# ArbPwrBoost_P5.net
KiCad netlist of a schematic drawn in Altium Designer
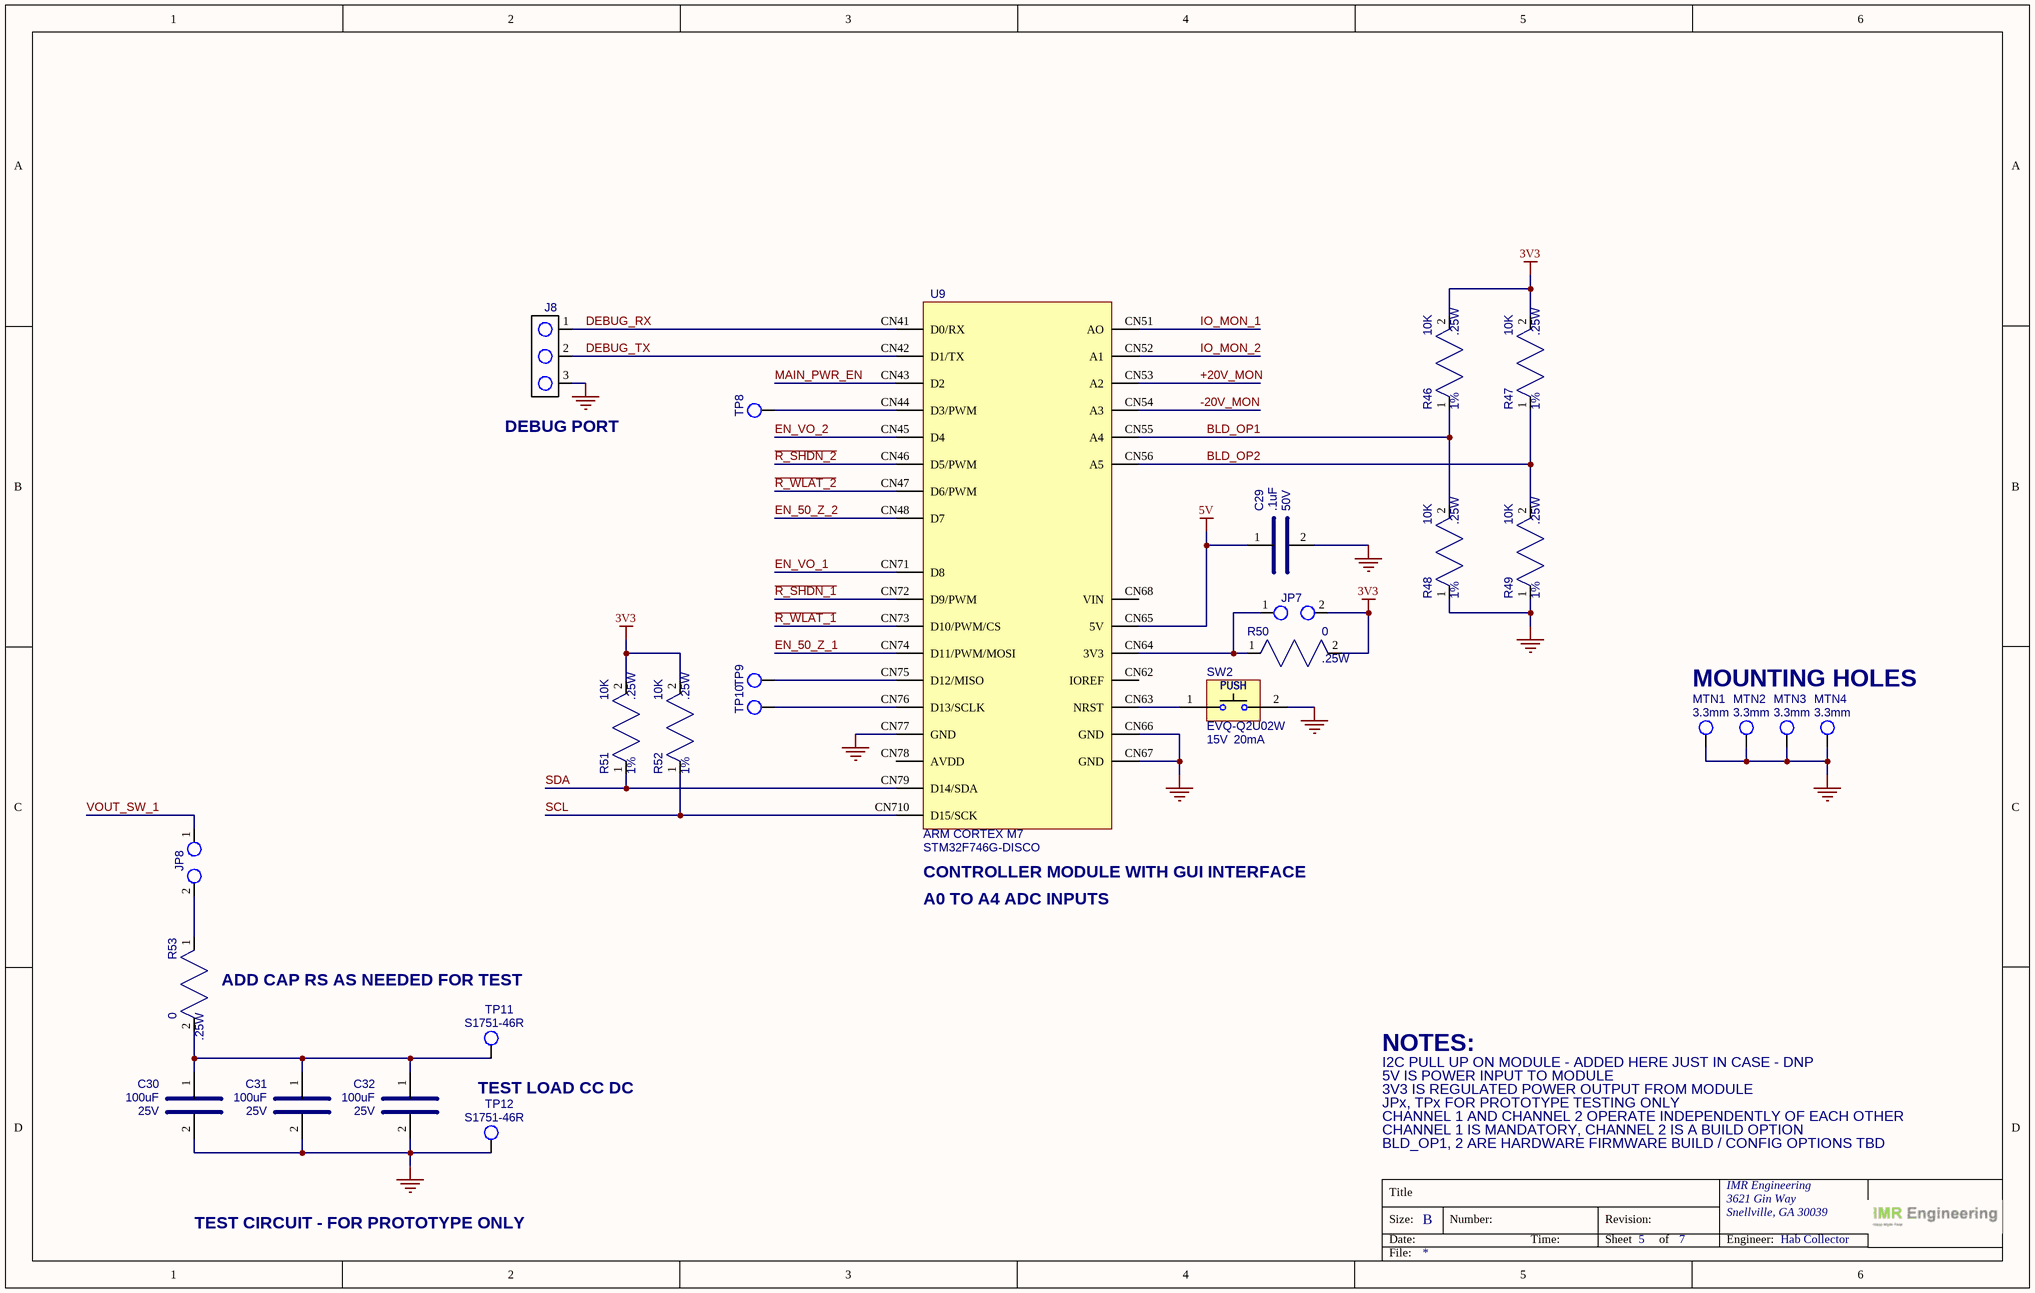
[diagram p0: ArbPwrBoost_P5.SchDoc]

(export (version "E")
  (design (tool "Eeschema 10.0.6"))
  (components
    (comp (ref "C29")
      (value ".1uF")
      (footprint "CAP_0805")
      (description "CAP CER 0.1UF 50V X7R 0805")
      (fields
        (field (name "MFG") "KYOCERA AVX")
        (field (name "VOLTAGE") "50V")
        (field (name "Comment") "KGM21NR71H104KT")
      )
      (libsource (lib "IMR_LIB_SCH_R2") (part "CAP_SMD_0.1UF_50V_0805"))
    )
    (comp (ref "C30")
      (value "100uF")
      (footprint "CAPC6153X670N")
      (description "CAP CER 100UF 25V X7S SMD")
      (fields
        (field (name "MFG") "Murata Electronics")
        (field (name "VOLTAGE") "25V")
        (field (name "Comment") "KCM55WC71E107MH13L")
      )
      (libsource (lib "IMR_LIB_SCH_R2") (part "CAP_SMD_100UF_25V_SMD"))
    )
    (comp (ref "C31")
      (value "100uF")
      (footprint "CAPC6153X670N")
      (description "CAP CER 100UF 25V X7S SMD")
      (fields
        (field (name "MFG") "Murata Electronics")
        (field (name "VOLTAGE") "25V")
        (field (name "Comment") "KCM55WC71E107MH13L")
      )
      (libsource (lib "IMR_LIB_SCH_R2") (part "CAP_SMD_100UF_25V_SMD"))
    )
    (comp (ref "C32")
      (value "100uF")
      (footprint "CAPC6153X670N")
      (description "CAP CER 100UF 25V X7S SMD")
      (fields
        (field (name "MFG") "Murata Electronics")
        (field (name "VOLTAGE") "25V")
        (field (name "Comment") "KCM55WC71E107MH13L")
      )
      (libsource (lib "IMR_LIB_SCH_R2") (part "CAP_SMD_100UF_25V_SMD"))
    )
    (comp (ref "J8")
      (value "PREC003SFAN-RC")
      (footprint "HDR_1X3_100MILL")
      (description "CONN HEADER VERT 3POS 2.54MM")
      (fields (field (name "MFG") "Sullins Connector Solutions"))
      (libsource (lib "IMR_LIB_SCH_R2") (part "CONN_HEADER_3P_100MIL_VERT"))
    )
    (comp (ref "JP7")
      (value "PREC002SFAN-RC")
      (footprint "HDR_1X2_100MILL")
      (description "CONN HEADER VERT 2POS 2.54MM")
      (fields (field (name "MFG") "Sullins Connector Solutions"))
      (libsource (lib "IMR_LIB_SCH_R2") (part "CONN_JUMPER_2P_100MIL_VERT"))
    )
    (comp (ref "JP8")
      (value "PREC002SFAN-RC")
      (footprint "HDR_1X2_100MILL")
      (description "CONN HEADER VERT 2POS 2.54MM")
      (fields (field (name "MFG") "Sullins Connector Solutions"))
      (libsource (lib "IMR_LIB_SCH_R2") (part "CONN_JUMPER_2P_100MIL_VERT"))
    )
    (comp (ref "MTN1")
      (value "~")
      (footprint "PMG_MT_HOLE_3.3MM")
      (description "MOUNTING HOLE 3.3MM")
      (fields (field (name "HOLE SIZE") "3.3mm"))
      (libsource (lib "IMR_LIB_SCH_R2") (part "MTN_HOLE_3.3MM"))
    )
    (comp (ref "MTN2")
      (value "~")
      (footprint "PMG_MT_HOLE_3.3MM")
      (description "MOUNTING HOLE 3.3MM")
      (fields (field (name "HOLE SIZE") "3.3mm"))
      (libsource (lib "IMR_LIB_SCH_R2") (part "MTN_HOLE_3.3MM"))
    )
    (comp (ref "MTN3")
      (value "~")
      (footprint "PMG_MT_HOLE_3.3MM")
      (description "MOUNTING HOLE 3.3MM")
      (fields (field (name "HOLE SIZE") "3.3mm"))
      (libsource (lib "IMR_LIB_SCH_R2") (part "MTN_HOLE_3.3MM"))
    )
    (comp (ref "MTN4")
      (value "~")
      (footprint "PMG_MT_HOLE_3.3MM")
      (description "MOUNTING HOLE 3.3MM")
      (fields (field (name "HOLE SIZE") "3.3mm"))
      (libsource (lib "IMR_LIB_SCH_R2") (part "MTN_HOLE_3.3MM"))
    )
    (comp (ref "R46")
      (value "10K")
      (footprint "RES_0805")
      (description "RES SMD 10K OHM 1% 1/4W 0805")
      (fields
        (field (name "MFG") "Yageo")
        (field (name "POWER") ".25W")
        (field (name "TOLERANCE") "1%")
        (field (name "Comment") "RC0805FR-7W10KL")
      )
      (libsource (lib "IMR_LIB_SCH_R2") (part "RES_SMD_10K_0805_1/4W_1%"))
    )
    (comp (ref "R47")
      (value "10K")
      (footprint "RES_0805")
      (description "RES SMD 10K OHM 1% 1/4W 0805")
      (fields
        (field (name "MFG") "Yageo")
        (field (name "POWER") ".25W")
        (field (name "TOLERANCE") "1%")
        (field (name "Comment") "RC0805FR-7W10KL")
      )
      (libsource (lib "IMR_LIB_SCH_R2") (part "RES_SMD_10K_0805_1/4W_1%"))
    )
    (comp (ref "R48")
      (value "10K")
      (footprint "RES_0805")
      (description "RES SMD 10K OHM 1% 1/4W 0805")
      (fields
        (field (name "MFG") "Yageo")
        (field (name "POWER") ".25W")
        (field (name "TOLERANCE") "1%")
        (field (name "Comment") "RC0805FR-7W10KL")
      )
      (libsource (lib "IMR_LIB_SCH_R2") (part "RES_SMD_10K_0805_1/4W_1%"))
    )
    (comp (ref "R49")
      (value "10K")
      (footprint "RES_0805")
      (description "RES SMD 10K OHM 1% 1/4W 0805")
      (fields
        (field (name "MFG") "Yageo")
        (field (name "POWER") ".25W")
        (field (name "TOLERANCE") "1%")
        (field (name "Comment") "RC0805FR-7W10KL")
      )
      (libsource (lib "IMR_LIB_SCH_R2") (part "RES_SMD_10K_0805_1/4W_1%"))
    )
    (comp (ref "R50")
      (value "0")
      (footprint "RES_0805")
      (description "RES SMD 0 OHM 1% 1/8W 0805")
      (fields (field (name "MFG") "Yageo") (field (name "TOLERANCE") "1%") (field (name "POWER") ".25W"))
      (libsource (lib "IMR_LIB_SCH_R2") (part "RES_SMD_0_0805_1/8W_1%"))
    )
    (comp (ref "R51")
      (value "10K")
      (footprint "RES_0805")
      (description "RES SMD 10K OHM 1% 1/4W 0805")
      (fields
        (field (name "MFG") "Yageo")
        (field (name "POWER") ".25W")
        (field (name "TOLERANCE") "1%")
        (field (name "Comment") "RC0805FR-7W10KL")
      )
      (libsource (lib "IMR_LIB_SCH_R2") (part "RES_SMD_10K_0805_1/4W_1%"))
    )
    (comp (ref "R52")
      (value "10K")
      (footprint "RES_0805")
      (description "RES SMD 10K OHM 1% 1/4W 0805")
      (fields
        (field (name "MFG") "Yageo")
        (field (name "POWER") ".25W")
        (field (name "TOLERANCE") "1%")
        (field (name "Comment") "RC0805FR-7W10KL")
      )
      (libsource (lib "IMR_LIB_SCH_R2") (part "RES_SMD_10K_0805_1/4W_1%"))
    )
    (comp (ref "R53")
      (value "0")
      (footprint "RES_0805")
      (description "RES SMD 0 OHM 1% 1/8W 0805")
      (fields (field (name "MFG") "Yageo") (field (name "TOLERANCE") "1%") (field (name "POWER") ".25W"))
      (libsource (lib "IMR_LIB_SCH_R2") (part "RES_SMD_0_0805_1/8W_1%"))
    )
    (comp (ref "SW2")
      (value "15V")
      (footprint "PANASONIC_EVQ-Q2U02W")
      (description "SWITCH TACTILE SPST-NO 0.02A 15V")
      (fields
        (field (name "MFG") "American Zettler")
        (field (name "MFG_PN") "EVQ-Q2U02W")
        (field (name "CURRENT") "20mA")
        (field (name "Comment") "EVQ-Q2U02W")
      )
      (libsource (lib "IMR_LIB_SCH_R2") (part "SWITCH_EVQ-Q2U02W"))
    )
    (comp (ref "TP8")
      (value "~")
      (footprint "TEST_POINT_20MIL_TH")
      (description "TEST POINT TH 20MIL HOLE")
      (libsource (lib "IMR_LIB_SCH_R2") (part "CONN_TEST_POINT_TH_PAD_20MIL"))
    )
    (comp (ref "TP9")
      (value "~")
      (footprint "TEST_POINT_20MIL_TH")
      (description "TEST POINT TH 20MIL HOLE")
      (libsource (lib "IMR_LIB_SCH_R2") (part "CONN_TEST_POINT_TH_PAD_20MIL"))
    )
    (comp (ref "TP10")
      (value "~")
      (footprint "TEST_POINT_20MIL_TH")
      (description "TEST POINT TH 20MIL HOLE")
      (libsource (lib "IMR_LIB_SCH_R2") (part "CONN_TEST_POINT_TH_PAD_20MIL"))
    )
    (comp (ref "TP11")
      (value "S1751-46R")
      (footprint "HARWIN_S1751")
      (description "PCB TEST POINT CONNECT")
      (fields (field (name "MFG") "Harwin Inc") (field (name "MFG_PN") "S1751-46R"))
      (libsource (lib "IMR_LIB_SCH_R2") (part "CONN_TEST_POINT_S1751-46R"))
    )
    (comp (ref "TP12")
      (value "S1751-46R")
      (footprint "HARWIN_S1751")
      (description "PCB TEST POINT CONNECT")
      (fields (field (name "MFG") "Harwin Inc") (field (name "MFG_PN") "S1751-46R"))
      (libsource (lib "IMR_LIB_SCH_R2") (part "CONN_TEST_POINT_S1751-46R"))
    )
    (comp (ref "U9")
      (value "ARM CORTEX M7")
      (footprint "STM32F746G-DISCO")
      (description "DISCOVERY STM32 F7 EVAL BRD")
      (fields
        (field (name "MFG") "ST Microlectronics")
        (field (name "MFG_PN") "STM32F746G-DISCO")
        (field (name "Comment") "STM32F746G-DISCO")
      )
      (libsource (lib "IMR_LIB_SCH_R2") (part "MODULE_STM32F746G-DISCO"))
    )
  )
  (nets
    (net (code "1") (name "/+20V_MON") (class "Default")
      (node (ref "U9") (pin "CN53") (pinfunction "A2_CN53") (pintype "passive"))
    )
    (net (code "2") (name "/-20V_MON") (class "Default")
      (node (ref "U9") (pin "CN54") (pinfunction "A3_CN54") (pintype "passive"))
    )
    (net (code "3") (name "/BLD_OP1") (class "Default")
      (node (ref "R46") (pin "1") (pinfunction "1_1") (pintype "passive"))
      (node (ref "R48") (pin "2") (pinfunction "2_2") (pintype "passive"))
      (node (ref "U9") (pin "CN55") (pinfunction "A4_CN55") (pintype "passive"))
    )
    (net (code "4") (name "/BLD_OP2") (class "Default")
      (node (ref "R47") (pin "1") (pinfunction "1_1") (pintype "passive"))
      (node (ref "R49") (pin "2") (pinfunction "2_2") (pintype "passive"))
      (node (ref "U9") (pin "CN56") (pinfunction "A5_CN56") (pintype "passive"))
    )
    (net (code "5") (name "/DEBUG_RX") (class "Default")
      (node (ref "J8") (pin "1") (pintype "passive"))
      (node (ref "U9") (pin "CN41") (pinfunction "D0/RX_CN41") (pintype "passive"))
    )
    (net (code "6") (name "/DEBUG_TX") (class "Default")
      (node (ref "J8") (pin "2") (pintype "passive"))
      (node (ref "U9") (pin "CN42") (pinfunction "D1/TX_CN42") (pintype "passive"))
    )
    (net (code "7") (name "/EN_50_Z_1") (class "Default")
      (node (ref "U9") (pin "CN74") (pinfunction "D11/PWM/MOSI_CN74") (pintype "passive"))
    )
    (net (code "8") (name "/EN_50_Z_2") (class "Default")
      (node (ref "U9") (pin "CN48") (pinfunction "D7_CN48") (pintype "passive"))
    )
    (net (code "9") (name "/EN_VO_1") (class "Default")
      (node (ref "U9") (pin "CN71") (pinfunction "D8_CN71") (pintype "passive"))
    )
    (net (code "10") (name "/EN_VO_2") (class "Default")
      (node (ref "U9") (pin "CN45") (pinfunction "D4_CN45") (pintype "passive"))
    )
    (net (code "11") (name "/IO_MON_1") (class "Default")
      (node (ref "U9") (pin "CN51") (pinfunction "AO_CN51") (pintype "passive"))
    )
    (net (code "12") (name "/IO_MON_2") (class "Default")
      (node (ref "U9") (pin "CN52") (pinfunction "A1_CN52") (pintype "passive"))
    )
    (net (code "13") (name "/MAIN_PWR_EN") (class "Default")
      (node (ref "U9") (pin "CN43") (pinfunction "D2_CN43") (pintype "passive"))
    )
    (net (code "14") (name "/SCL") (class "Default")
      (node (ref "R52") (pin "1") (pinfunction "1_1") (pintype "passive"))
      (node (ref "U9") (pin "CN710") (pinfunction "D15/SCK_CN710") (pintype "passive"))
    )
    (net (code "15") (name "/SDA") (class "Default")
      (node (ref "R51") (pin "1") (pinfunction "1_1") (pintype "passive"))
      (node (ref "U9") (pin "CN79") (pinfunction "D14/SDA_CN79") (pintype "passive"))
    )
    (net (code "16") (name "/VOUT_SW_1") (class "Default") (node (ref "JP8") (pin "1") (pintype "passive")))
    (net (code "17") (name "/~{R_SHDN_1}") (class "Default")
      (node (ref "U9") (pin "CN72") (pinfunction "D9/PWM_CN72") (pintype "passive"))
    )
    (net (code "18") (name "/~{R_SHDN_2}") (class "Default")
      (node (ref "U9") (pin "CN46") (pinfunction "D5/PWM_CN46") (pintype "passive"))
    )
    (net (code "19") (name "/~{R_WLAT_1}") (class "Default")
      (node (ref "U9") (pin "CN73") (pinfunction "D10/PWM/CS_CN73") (pintype "passive"))
    )
    (net (code "20") (name "/~{R_WLAT_2}") (class "Default")
      (node (ref "U9") (pin "CN47") (pinfunction "D6/PWM_CN47") (pintype "passive"))
    )
    (net (code "21") (name "3V3") (class "Default")
      (node (ref "JP7") (pin "2") (pintype "passive"))
      (node (ref "R46") (pin "2") (pinfunction "2_2") (pintype "passive"))
      (node (ref "R47") (pin "2") (pinfunction "2_2") (pintype "passive"))
      (node (ref "R50") (pin "2") (pinfunction "2_2") (pintype "passive"))
      (node (ref "R51") (pin "2") (pinfunction "2_2") (pintype "passive"))
      (node (ref "R52") (pin "2") (pinfunction "2_2") (pintype "passive"))
    )
    (net (code "22") (name "5V") (class "Default")
      (node (ref "C29") (pin "1") (pinfunction "1_1") (pintype "passive"))
      (node (ref "U9") (pin "CN65") (pinfunction "5V_CN65") (pintype "passive"))
    )
    (net (code "23") (name "GND") (class "Default")
      (node (ref "C29") (pin "2") (pinfunction "2_2") (pintype "passive"))
      (node (ref "C30") (pin "2") (pinfunction "2_2") (pintype "passive"))
      (node (ref "C31") (pin "2") (pinfunction "2_2") (pintype "passive"))
      (node (ref "C32") (pin "2") (pinfunction "2_2") (pintype "passive"))
      (node (ref "J8") (pin "3") (pintype "passive"))
      (node (ref "MTN1") (pin "1") (pintype "passive"))
      (node (ref "MTN2") (pin "1") (pintype "passive"))
      (node (ref "MTN3") (pin "1") (pintype "passive"))
      (node (ref "MTN4") (pin "1") (pintype "passive"))
      (node (ref "R48") (pin "1") (pinfunction "1_1") (pintype "passive"))
      (node (ref "R49") (pin "1") (pinfunction "1_1") (pintype "passive"))
      (node (ref "SW2") (pin "2") (pinfunction "B'_2") (pintype "passive"))
      (node (ref "TP12") (pin "1") (pintype "passive"))
      (node (ref "U9") (pin "CN66") (pinfunction "GND_CN66") (pintype "passive"))
      (node (ref "U9") (pin "CN67") (pinfunction "GND_CN67") (pintype "passive"))
      (node (ref "U9") (pin "CN77") (pinfunction "GND_CN77") (pintype "passive"))
    )
    (net (code "24") (name "Net-(C30-Pad1)") (class "Default")
      (node (ref "C30") (pin "1") (pinfunction "1_1") (pintype "passive"))
      (node (ref "C31") (pin "1") (pinfunction "1_1") (pintype "passive"))
      (node (ref "C32") (pin "1") (pinfunction "1_1") (pintype "passive"))
      (node (ref "R53") (pin "2") (pinfunction "2_2") (pintype "passive"))
      (node (ref "TP11") (pin "1") (pintype "passive"))
    )
    (net (code "25") (name "Net-(JP8-Pad2)") (class "Default")
      (node (ref "JP8") (pin "2") (pintype "passive"))
      (node (ref "R53") (pin "1") (pinfunction "1_1") (pintype "passive"))
    )
    (net (code "26") (name "Net-(SW2-B)") (class "Default")
      (node (ref "SW2") (pin "1") (pinfunction "B_1") (pintype "passive"))
      (node (ref "U9") (pin "CN63") (pinfunction "NRST_CN63") (pintype "passive"))
    )
    (net (code "27") (name "Net-(U9-3V3)") (class "Default")
      (node (ref "JP7") (pin "1") (pintype "passive"))
      (node (ref "R50") (pin "1") (pinfunction "1_1") (pintype "passive"))
      (node (ref "U9") (pin "CN64") (pinfunction "3V3_CN64") (pintype "passive"))
    )
    (net (code "28") (name "Net-(U9-D3{slash}PWM)") (class "Default")
      (node (ref "TP8") (pin "1") (pintype "passive"))
      (node (ref "U9") (pin "CN44") (pinfunction "D3/PWM_CN44") (pintype "passive"))
    )
    (net (code "29") (name "Net-(U9-D12{slash}MISO)") (class "Default")
      (node (ref "TP9") (pin "1") (pintype "passive"))
      (node (ref "U9") (pin "CN75") (pinfunction "D12/MISO_CN75") (pintype "passive"))
    )
    (net (code "30") (name "Net-(U9-D13{slash}SCLK)") (class "Default")
      (node (ref "TP10") (pin "1") (pintype "passive"))
      (node (ref "U9") (pin "CN76") (pinfunction "D13/SCLK_CN76") (pintype "passive"))
    )
    (net (code "31") (name "unconnected-(U9-AVDD-PadCN78)") (class "Default")
      (node (ref "U9") (pin "CN78") (pinfunction "AVDD_CN78") (pintype "passive"))
    )
    (net (code "32") (name "unconnected-(U9-IOREF-PadCN62)") (class "Default")
      (node (ref "U9") (pin "CN62") (pinfunction "IOREF_CN62") (pintype "passive"))
    )
    (net (code "33") (name "unconnected-(U9-VIN-PadCN68)") (class "Default")
      (node (ref "U9") (pin "CN68") (pinfunction "VIN_CN68") (pintype "passive"))
    )
  )
)
